# PDMschemE-Car2018.net
KiCad netlist of a schematic drawn in EAGLE
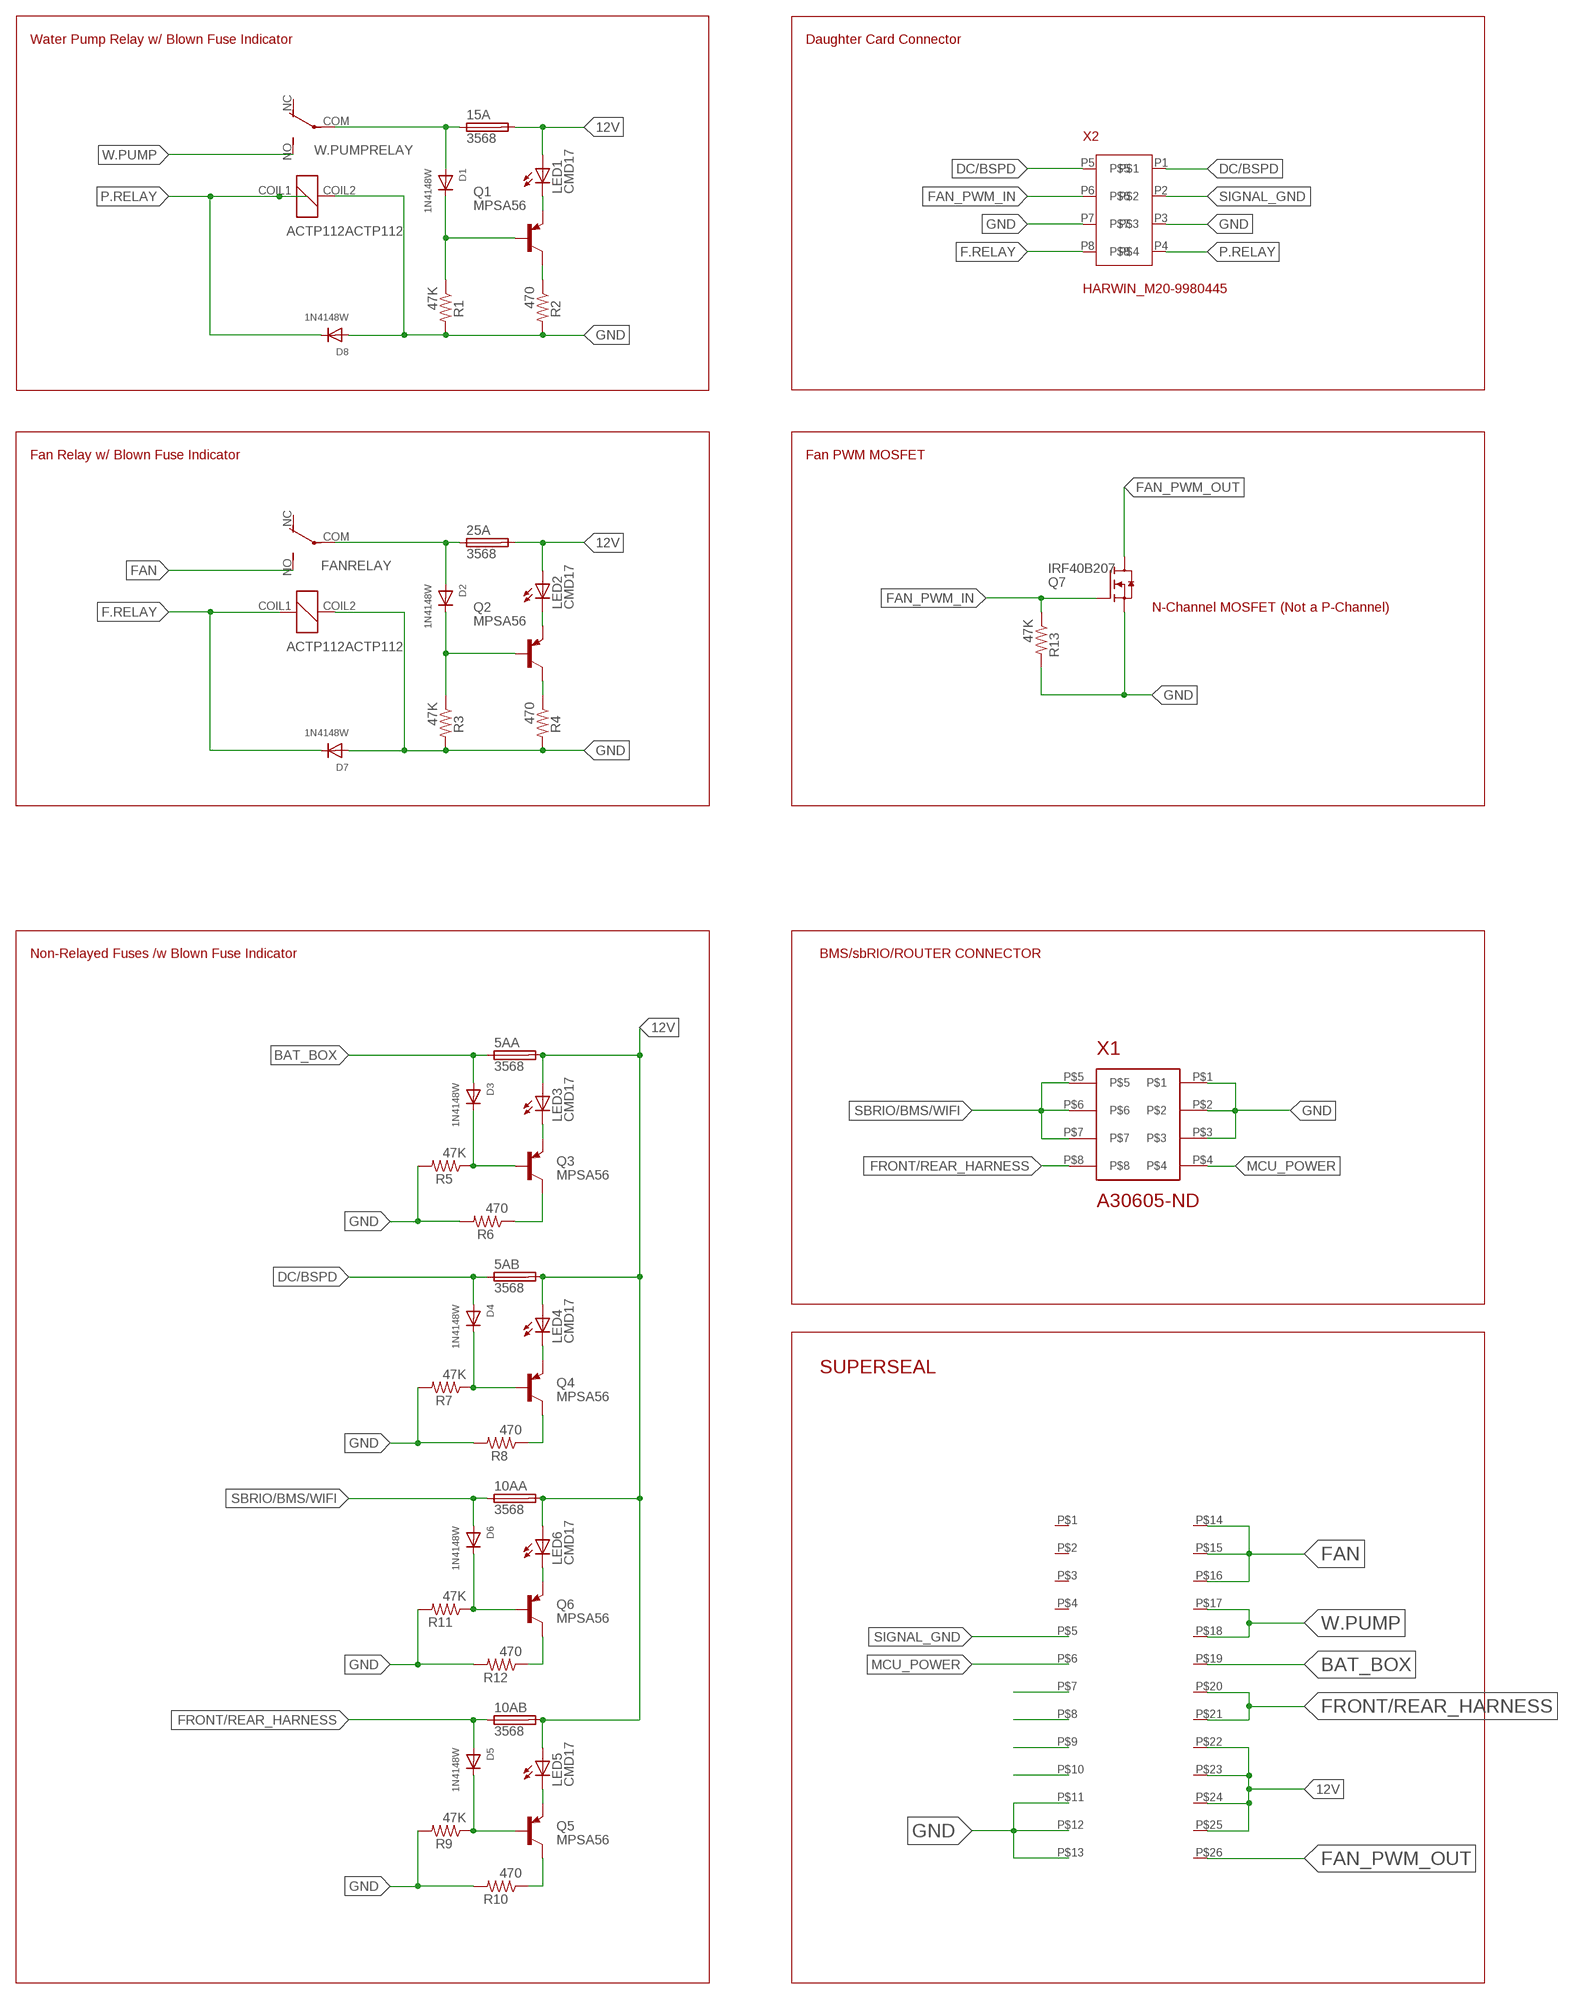
[diagram p0: schematic, sheet 1]

(export (version "E")
  (design (tool "Eeschema 10.0.6"))
  (components
    (comp (ref "5AA")
      (value "3568")
      (footprint "eagle-import:3568")
      (libsource (lib "eagle-import") (part "3568"))
    )
    (comp (ref "5AB")
      (value "3568")
      (footprint "eagle-import:3568")
      (libsource (lib "eagle-import") (part "3568"))
    )
    (comp (ref "10AA")
      (value "3568")
      (footprint "eagle-import:3568")
      (libsource (lib "eagle-import") (part "3568"))
    )
    (comp (ref "10AB")
      (value "3568")
      (footprint "eagle-import:3568")
      (libsource (lib "eagle-import") (part "3568"))
    )
    (comp (ref "15A")
      (value "3568")
      (footprint "eagle-import:3568")
      (libsource (lib "eagle-import") (part "3568"))
    )
    (comp (ref "25A")
      (value "3568")
      (footprint "eagle-import:3568")
      (libsource (lib "eagle-import") (part "3568"))
    )
    (comp (ref "D1")
      (value "1N4148W")
      (footprint "eagle-import:SOD-123")
      (libsource (lib "eagle-import") (part "DIODESOD-123"))
    )
    (comp (ref "D2")
      (value "1N4148W")
      (footprint "eagle-import:SOD-123")
      (libsource (lib "eagle-import") (part "DIODESOD-123"))
    )
    (comp (ref "D3")
      (value "1N4148W")
      (footprint "eagle-import:SOD-123")
      (libsource (lib "eagle-import") (part "DIODESOD-123"))
    )
    (comp (ref "D4")
      (value "1N4148W")
      (footprint "eagle-import:SOD-123")
      (libsource (lib "eagle-import") (part "DIODESOD-123"))
    )
    (comp (ref "D5")
      (value "1N4148W")
      (footprint "eagle-import:SOD-123")
      (libsource (lib "eagle-import") (part "DIODESOD-123"))
    )
    (comp (ref "D6")
      (value "1N4148W")
      (footprint "eagle-import:SOD-123")
      (libsource (lib "eagle-import") (part "DIODESOD-123"))
    )
    (comp (ref "D7")
      (value "1N4148W")
      (footprint "eagle-import:SOD-123")
      (libsource (lib "eagle-import") (part "DIODESOD-123"))
    )
    (comp (ref "D8")
      (value "1N4148W")
      (footprint "eagle-import:SOD-123")
      (libsource (lib "eagle-import") (part "DIODESOD-123"))
    )
    (comp (ref "FANRELAY")
      (value "ACTP112ACTP112")
      (footprint "eagle-import:ACTP112")
      (libsource (lib "eagle-import") (part "ACTP112ACTP112"))
    )
    (comp (ref "LED1")
      (value "CMD17")
      (footprint "eagle-import:CHIPLED_0805")
      (libsource (lib "eagle-import") (part "LEDCHIPLED_0805"))
    )
    (comp (ref "LED2")
      (value "CMD17")
      (footprint "eagle-import:CHIPLED_0805")
      (libsource (lib "eagle-import") (part "LEDCHIPLED_0805"))
    )
    (comp (ref "LED3")
      (value "CMD17")
      (footprint "eagle-import:CHIPLED_0805")
      (libsource (lib "eagle-import") (part "LEDCHIPLED_0805"))
    )
    (comp (ref "LED4")
      (value "CMD17")
      (footprint "eagle-import:CHIPLED_0805")
      (libsource (lib "eagle-import") (part "LEDCHIPLED_0805"))
    )
    (comp (ref "LED5")
      (value "CMD17")
      (footprint "eagle-import:CHIPLED_0805")
      (libsource (lib "eagle-import") (part "LEDCHIPLED_0805"))
    )
    (comp (ref "LED6")
      (value "CMD17")
      (footprint "eagle-import:CHIPLED_0805")
      (libsource (lib "eagle-import") (part "LEDCHIPLED_0805"))
    )
    (comp (ref "Q1")
      (value "MPSA56")
      (footprint "eagle-import:TO92-CBE")
      (libsource (lib "eagle-import") (part "MPSA56"))
    )
    (comp (ref "Q2")
      (value "MPSA56")
      (footprint "eagle-import:TO92-CBE")
      (libsource (lib "eagle-import") (part "MPSA56"))
    )
    (comp (ref "Q3")
      (value "MPSA56")
      (footprint "eagle-import:TO92-CBE")
      (libsource (lib "eagle-import") (part "MPSA56"))
    )
    (comp (ref "Q4")
      (value "MPSA56")
      (footprint "eagle-import:TO92-CBE")
      (libsource (lib "eagle-import") (part "MPSA56"))
    )
    (comp (ref "Q5")
      (value "MPSA56")
      (footprint "eagle-import:TO92-CBE")
      (libsource (lib "eagle-import") (part "MPSA56"))
    )
    (comp (ref "Q6")
      (value "MPSA56")
      (footprint "eagle-import:TO92-CBE")
      (libsource (lib "eagle-import") (part "MPSA56"))
    )
    (comp (ref "Q7")
      (value "IRF40B207")
      (footprint "eagle-import:TO220-3")
      (libsource (lib "eagle-import") (part "IRF40B207"))
    )
    (comp (ref "R1")
      (value "47K")
      (footprint "eagle-import:R1206")
      (libsource (lib "eagle-import") (part "R-US_R1206"))
    )
    (comp (ref "R2")
      (value "470")
      (footprint "eagle-import:R1206")
      (libsource (lib "eagle-import") (part "R-US_R1206"))
    )
    (comp (ref "R3")
      (value "47K")
      (footprint "eagle-import:R1206")
      (libsource (lib "eagle-import") (part "R-US_R1206"))
    )
    (comp (ref "R4")
      (value "470")
      (footprint "eagle-import:R1206")
      (libsource (lib "eagle-import") (part "R-US_R1206"))
    )
    (comp (ref "R5")
      (value "47K")
      (footprint "eagle-import:R1206")
      (libsource (lib "eagle-import") (part "R-US_R1206"))
    )
    (comp (ref "R6")
      (value "470")
      (footprint "eagle-import:R1206")
      (libsource (lib "eagle-import") (part "R-US_R1206"))
    )
    (comp (ref "R7")
      (value "47K")
      (footprint "eagle-import:R1206")
      (libsource (lib "eagle-import") (part "R-US_R1206"))
    )
    (comp (ref "R8")
      (value "470")
      (footprint "eagle-import:R1206")
      (libsource (lib "eagle-import") (part "R-US_R1206"))
    )
    (comp (ref "R9")
      (value "47K")
      (footprint "eagle-import:R1206")
      (libsource (lib "eagle-import") (part "R-US_R1206"))
    )
    (comp (ref "R10")
      (value "470")
      (footprint "eagle-import:R1206")
      (libsource (lib "eagle-import") (part "R-US_R1206"))
    )
    (comp (ref "R11")
      (value "47K")
      (footprint "eagle-import:R1206")
      (libsource (lib "eagle-import") (part "R-US_R1206"))
    )
    (comp (ref "R12")
      (value "470")
      (footprint "eagle-import:R1206")
      (libsource (lib "eagle-import") (part "R-US_R1206"))
    )
    (comp (ref "R13")
      (value "47K")
      (footprint "eagle-import:R1206")
      (libsource (lib "eagle-import") (part "R-US_R1206"))
    )
    (comp (ref "U$4")
      (value "SUPERSEAL1.0_26POS_2ROW")
      (footprint "eagle-import:SUPERSEAL1.0_26POS_2ROW")
      (libsource (lib "eagle-import") (part "SUPERSEAL1.0_26POS_2ROW"))
    )
    (comp (ref "W.PUMPRELAY")
      (value "ACTP112ACTP112")
      (footprint "eagle-import:ACTP112")
      (libsource (lib "eagle-import") (part "ACTP112ACTP112"))
    )
    (comp (ref "X1")
      (value "A30605-ND")
      (footprint "eagle-import:A30605-ND")
      (libsource (lib "eagle-import") (part "A30605-ND"))
    )
    (comp (ref "X2")
      (value "HARWIN_M20-9980445")
      (footprint "eagle-import:HARWIN_M20-9980445")
      (libsource (lib "eagle-import") (part "HARWIN_M20-9980445"))
    )
  )
  (nets
    (net (code "1") (name "12V") (class "Default")
      (node (ref "10AA") (pin "3") (pinfunction "2_3") (pintype "passive"))
      (node (ref "10AA") (pin "4") (pinfunction "2_4") (pintype "passive"))
      (node (ref "10AB") (pin "3") (pinfunction "2_3") (pintype "passive"))
      (node (ref "10AB") (pin "4") (pinfunction "2_4") (pintype "passive"))
      (node (ref "15A") (pin "3") (pinfunction "2_3") (pintype "passive"))
      (node (ref "15A") (pin "4") (pinfunction "2_4") (pintype "passive"))
      (node (ref "25A") (pin "3") (pinfunction "2_3") (pintype "passive"))
      (node (ref "25A") (pin "4") (pinfunction "2_4") (pintype "passive"))
      (node (ref "5AA") (pin "3") (pinfunction "2_3") (pintype "passive"))
      (node (ref "5AA") (pin "4") (pinfunction "2_4") (pintype "passive"))
      (node (ref "5AB") (pin "3") (pinfunction "2_3") (pintype "passive"))
      (node (ref "5AB") (pin "4") (pinfunction "2_4") (pintype "passive"))
      (node (ref "LED1") (pin "A") (pinfunction "A_A") (pintype "passive"))
      (node (ref "LED2") (pin "A") (pinfunction "A_A") (pintype "passive"))
      (node (ref "LED3") (pin "A") (pinfunction "A_A") (pintype "passive"))
      (node (ref "LED4") (pin "A") (pinfunction "A_A") (pintype "passive"))
      (node (ref "LED5") (pin "A") (pinfunction "A_A") (pintype "passive"))
      (node (ref "LED6") (pin "A") (pinfunction "A_A") (pintype "passive"))
      (node (ref "U$4") (pin "P$22") (pinfunction "B22_P$22") (pintype "bidirectional"))
      (node (ref "U$4") (pin "P$23") (pinfunction "B23_P$23") (pintype "bidirectional"))
      (node (ref "U$4") (pin "P$24") (pinfunction "B24_P$24") (pintype "bidirectional"))
      (node (ref "U$4") (pin "P$25") (pinfunction "B25_P$25") (pintype "bidirectional"))
    )
    (net (code "2") (name "BAT_BOX") (class "Default")
      (node (ref "5AA") (pin "1") (pinfunction "1_1") (pintype "passive"))
      (node (ref "5AA") (pin "2") (pinfunction "1_2") (pintype "passive"))
      (node (ref "D3") (pin "A") (pinfunction "A_A") (pintype "passive"))
      (node (ref "U$4") (pin "P$19") (pinfunction "B19_P$19") (pintype "bidirectional"))
    )
    (net (code "3") (name "DC{slash}BSPD") (class "Default")
      (node (ref "5AB") (pin "1") (pinfunction "1_1") (pintype "passive"))
      (node (ref "5AB") (pin "2") (pinfunction "1_2") (pintype "passive"))
      (node (ref "D4") (pin "A") (pinfunction "A_A") (pintype "passive"))
      (node (ref "X2") (pin "P1") (pinfunction "P$1_P1") (pintype "bidirectional"))
      (node (ref "X2") (pin "P5") (pinfunction "P$5_P5") (pintype "bidirectional"))
    )
    (net (code "4") (name "F.RELAY") (class "Default")
      (node (ref "D7") (pin "C") (pinfunction "C_C") (pintype "passive"))
      (node (ref "FANRELAY") (pin "COIL1") (pinfunction "COIL1_COIL1") (pintype "passive"))
      (node (ref "X2") (pin "P8") (pinfunction "P$8_P8") (pintype "bidirectional"))
    )
    (net (code "5") (name "FAN") (class "Default")
      (node (ref "FANRELAY") (pin "NO") (pinfunction "NO_NO") (pintype "passive"))
      (node (ref "U$4") (pin "P$14") (pinfunction "B14_P$14") (pintype "bidirectional"))
      (node (ref "U$4") (pin "P$15") (pinfunction "B15_P$15") (pintype "bidirectional"))
      (node (ref "U$4") (pin "P$16") (pinfunction "B16_P$16") (pintype "bidirectional"))
    )
    (net (code "6") (name "FAN_PWM_IN") (class "Default")
      (node (ref "Q7") (pin "G") (pinfunction "G_G") (pintype "passive"))
      (node (ref "R13") (pin "1") (pinfunction "1_1") (pintype "passive"))
      (node (ref "X2") (pin "P6") (pinfunction "P$6_P6") (pintype "bidirectional"))
    )
    (net (code "7") (name "FAN_PWM_OUT") (class "Default")
      (node (ref "Q7") (pin "D") (pinfunction "D_D") (pintype "passive"))
      (node (ref "U$4") (pin "P$26") (pinfunction "B26_P$26") (pintype "bidirectional"))
    )
    (net (code "8") (name "FRONT{slash}REAR_HARNESS") (class "Default")
      (node (ref "10AB") (pin "1") (pinfunction "1_1") (pintype "passive"))
      (node (ref "10AB") (pin "2") (pinfunction "1_2") (pintype "passive"))
      (node (ref "D5") (pin "A") (pinfunction "A_A") (pintype "passive"))
      (node (ref "U$4") (pin "P$20") (pinfunction "B20_P$20") (pintype "bidirectional"))
      (node (ref "U$4") (pin "P$21") (pinfunction "B21_P$21") (pintype "bidirectional"))
      (node (ref "X1") (pin "P$8") (pinfunction "P$8_P$8") (pintype "bidirectional"))
    )
    (net (code "9") (name "GND") (class "Default")
      (node (ref "D7") (pin "A") (pinfunction "A_A") (pintype "passive"))
      (node (ref "D8") (pin "A") (pinfunction "A_A") (pintype "passive"))
      (node (ref "FANRELAY") (pin "COIL2") (pinfunction "COIL2_COIL2") (pintype "passive"))
      (node (ref "Q7") (pin "S") (pinfunction "S_S") (pintype "passive"))
      (node (ref "R1") (pin "2") (pinfunction "2_2") (pintype "passive"))
      (node (ref "R10") (pin "2") (pinfunction "2_2") (pintype "passive"))
      (node (ref "R11") (pin "2") (pinfunction "2_2") (pintype "passive"))
      (node (ref "R12") (pin "2") (pinfunction "2_2") (pintype "passive"))
      (node (ref "R13") (pin "2") (pinfunction "2_2") (pintype "passive"))
      (node (ref "R2") (pin "2") (pinfunction "2_2") (pintype "passive"))
      (node (ref "R3") (pin "2") (pinfunction "2_2") (pintype "passive"))
      (node (ref "R4") (pin "2") (pinfunction "2_2") (pintype "passive"))
      (node (ref "R5") (pin "2") (pinfunction "2_2") (pintype "passive"))
      (node (ref "R6") (pin "2") (pinfunction "2_2") (pintype "passive"))
      (node (ref "R7") (pin "2") (pinfunction "2_2") (pintype "passive"))
      (node (ref "R8") (pin "2") (pinfunction "2_2") (pintype "passive"))
      (node (ref "R9") (pin "2") (pinfunction "2_2") (pintype "passive"))
      (node (ref "U$4") (pin "P$11") (pinfunction "B11_P$11") (pintype "bidirectional"))
      (node (ref "U$4") (pin "P$12") (pinfunction "B12_P$12") (pintype "bidirectional"))
      (node (ref "U$4") (pin "P$13") (pinfunction "B13_P$13") (pintype "bidirectional"))
      (node (ref "W.PUMPRELAY") (pin "COIL2") (pinfunction "COIL2_COIL2") (pintype "passive"))
      (node (ref "X1") (pin "P$1") (pinfunction "P$1_P$1") (pintype "bidirectional"))
      (node (ref "X1") (pin "P$2") (pinfunction "P$2_P$2") (pintype "bidirectional"))
      (node (ref "X1") (pin "P$3") (pinfunction "P$3_P$3") (pintype "bidirectional"))
      (node (ref "X2") (pin "P3") (pinfunction "P$3_P3") (pintype "bidirectional"))
      (node (ref "X2") (pin "P7") (pinfunction "P$7_P7") (pintype "bidirectional"))
    )
    (net (code "10") (name "MCU_POWER") (class "Default")
      (node (ref "U$4") (pin "P$6") (pinfunction "B6_P$6") (pintype "bidirectional"))
      (node (ref "X1") (pin "P$4") (pinfunction "P$4_P$4") (pintype "bidirectional"))
    )
    (net (code "11") (name "Net-(15A-1-Pad2)") (class "Default")
      (node (ref "15A") (pin "1") (pinfunction "1_1") (pintype "passive"))
      (node (ref "15A") (pin "2") (pinfunction "1_2") (pintype "passive"))
      (node (ref "D1") (pin "A") (pinfunction "A_A") (pintype "passive"))
      (node (ref "W.PUMPRELAY") (pin "COM") (pinfunction "COM_COM") (pintype "passive"))
    )
    (net (code "12") (name "Net-(25A-1-Pad2)") (class "Default")
      (node (ref "25A") (pin "1") (pinfunction "1_1") (pintype "passive"))
      (node (ref "25A") (pin "2") (pinfunction "1_2") (pintype "passive"))
      (node (ref "D2") (pin "A") (pinfunction "A_A") (pintype "passive"))
      (node (ref "FANRELAY") (pin "COM") (pinfunction "COM_COM") (pintype "passive"))
    )
    (net (code "13") (name "Net-(D1-PadC)") (class "Default")
      (node (ref "D1") (pin "C") (pinfunction "C_C") (pintype "passive"))
      (node (ref "Q1") (pin "B") (pinfunction "B_B") (pintype "passive"))
      (node (ref "R1") (pin "1") (pinfunction "1_1") (pintype "passive"))
    )
    (net (code "14") (name "Net-(D2-PadC)") (class "Default")
      (node (ref "D2") (pin "C") (pinfunction "C_C") (pintype "passive"))
      (node (ref "Q2") (pin "B") (pinfunction "B_B") (pintype "passive"))
      (node (ref "R3") (pin "1") (pinfunction "1_1") (pintype "passive"))
    )
    (net (code "15") (name "Net-(D3-PadC)") (class "Default")
      (node (ref "D3") (pin "C") (pinfunction "C_C") (pintype "passive"))
      (node (ref "Q3") (pin "B") (pinfunction "B_B") (pintype "passive"))
      (node (ref "R5") (pin "1") (pinfunction "1_1") (pintype "passive"))
    )
    (net (code "16") (name "Net-(D4-PadC)") (class "Default")
      (node (ref "D4") (pin "C") (pinfunction "C_C") (pintype "passive"))
      (node (ref "Q4") (pin "B") (pinfunction "B_B") (pintype "passive"))
      (node (ref "R7") (pin "1") (pinfunction "1_1") (pintype "passive"))
    )
    (net (code "17") (name "Net-(D5-PadC)") (class "Default")
      (node (ref "D5") (pin "C") (pinfunction "C_C") (pintype "passive"))
      (node (ref "Q5") (pin "B") (pinfunction "B_B") (pintype "passive"))
      (node (ref "R9") (pin "1") (pinfunction "1_1") (pintype "passive"))
    )
    (net (code "18") (name "Net-(D6-PadC)") (class "Default")
      (node (ref "D6") (pin "C") (pinfunction "C_C") (pintype "passive"))
      (node (ref "Q6") (pin "B") (pinfunction "B_B") (pintype "passive"))
      (node (ref "R11") (pin "1") (pinfunction "1_1") (pintype "passive"))
    )
    (net (code "19") (name "Net-(LED1-PadC)") (class "Default")
      (node (ref "LED1") (pin "C") (pinfunction "C_C") (pintype "passive"))
      (node (ref "Q1") (pin "E") (pinfunction "E_E") (pintype "passive"))
    )
    (net (code "20") (name "Net-(LED2-PadC)") (class "Default")
      (node (ref "LED2") (pin "C") (pinfunction "C_C") (pintype "passive"))
      (node (ref "Q2") (pin "E") (pinfunction "E_E") (pintype "passive"))
    )
    (net (code "21") (name "Net-(LED3-PadC)") (class "Default")
      (node (ref "LED3") (pin "C") (pinfunction "C_C") (pintype "passive"))
      (node (ref "Q3") (pin "E") (pinfunction "E_E") (pintype "passive"))
    )
    (net (code "22") (name "Net-(LED4-PadC)") (class "Default")
      (node (ref "LED4") (pin "C") (pinfunction "C_C") (pintype "passive"))
      (node (ref "Q4") (pin "E") (pinfunction "E_E") (pintype "passive"))
    )
    (net (code "23") (name "Net-(LED5-PadC)") (class "Default")
      (node (ref "LED5") (pin "C") (pinfunction "C_C") (pintype "passive"))
      (node (ref "Q5") (pin "E") (pinfunction "E_E") (pintype "passive"))
    )
    (net (code "24") (name "Net-(LED6-PadC)") (class "Default")
      (node (ref "LED6") (pin "C") (pinfunction "C_C") (pintype "passive"))
      (node (ref "Q6") (pin "E") (pinfunction "E_E") (pintype "passive"))
    )
    (net (code "25") (name "Net-(Q1-PadC)") (class "Default")
      (node (ref "Q1") (pin "C") (pinfunction "C_C") (pintype "passive"))
      (node (ref "R2") (pin "1") (pinfunction "1_1") (pintype "passive"))
    )
    (net (code "26") (name "Net-(Q2-PadC)") (class "Default")
      (node (ref "Q2") (pin "C") (pinfunction "C_C") (pintype "passive"))
      (node (ref "R4") (pin "1") (pinfunction "1_1") (pintype "passive"))
    )
    (net (code "27") (name "Net-(Q3-PadC)") (class "Default")
      (node (ref "Q3") (pin "C") (pinfunction "C_C") (pintype "passive"))
      (node (ref "R6") (pin "1") (pinfunction "1_1") (pintype "passive"))
    )
    (net (code "28") (name "Net-(Q4-PadC)") (class "Default")
      (node (ref "Q4") (pin "C") (pinfunction "C_C") (pintype "passive"))
      (node (ref "R8") (pin "1") (pinfunction "1_1") (pintype "passive"))
    )
    (net (code "29") (name "Net-(Q5-PadC)") (class "Default")
      (node (ref "Q5") (pin "C") (pinfunction "C_C") (pintype "passive"))
      (node (ref "R10") (pin "1") (pinfunction "1_1") (pintype "passive"))
    )
    (net (code "30") (name "Net-(Q6-PadC)") (class "Default")
      (node (ref "Q6") (pin "C") (pinfunction "C_C") (pintype "passive"))
      (node (ref "R12") (pin "1") (pinfunction "1_1") (pintype "passive"))
    )
    (net (code "31") (name "P.RELAY") (class "Default")
      (node (ref "D8") (pin "C") (pinfunction "C_C") (pintype "passive"))
      (node (ref "W.PUMPRELAY") (pin "COIL1") (pinfunction "COIL1_COIL1") (pintype "passive"))
      (node (ref "X2") (pin "P4") (pinfunction "P$4_P4") (pintype "bidirectional"))
    )
    (net (code "32") (name "SBRIO{slash}BMS{slash}WIFI") (class "Default")
      (node (ref "10AA") (pin "1") (pinfunction "1_1") (pintype "passive"))
      (node (ref "10AA") (pin "2") (pinfunction "1_2") (pintype "passive"))
      (node (ref "D6") (pin "A") (pinfunction "A_A") (pintype "passive"))
      (node (ref "X1") (pin "P$5") (pinfunction "P$5_P$5") (pintype "bidirectional"))
      (node (ref "X1") (pin "P$6") (pinfunction "P$6_P$6") (pintype "bidirectional"))
      (node (ref "X1") (pin "P$7") (pinfunction "P$7_P$7") (pintype "bidirectional"))
    )
    (net (code "33") (name "SIGNAL_GND") (class "Default")
      (node (ref "U$4") (pin "P$5") (pinfunction "B5_P$5") (pintype "bidirectional"))
      (node (ref "X2") (pin "P2") (pinfunction "P$2_P2") (pintype "bidirectional"))
    )
    (net (code "34") (name "W.PUMP") (class "Default")
      (node (ref "U$4") (pin "P$17") (pinfunction "B17_P$17") (pintype "bidirectional"))
      (node (ref "U$4") (pin "P$18") (pinfunction "B18_P$18") (pintype "bidirectional"))
      (node (ref "W.PUMPRELAY") (pin "NO") (pinfunction "NO_NO") (pintype "passive"))
    )
    (net (code "35") (name "unconnected-(FANRELAY-PadNC)") (class "Default")
      (node (ref "FANRELAY") (pin "NC") (pinfunction "NC_NC") (pintype "passive"))
    )
    (net (code "36") (name "unconnected-(U$4-B1-PadP$1)") (class "Default")
      (node (ref "U$4") (pin "P$1") (pinfunction "B1_P$1") (pintype "bidirectional"))
    )
    (net (code "37") (name "unconnected-(U$4-B2-PadP$2)") (class "Default")
      (node (ref "U$4") (pin "P$2") (pinfunction "B2_P$2") (pintype "bidirectional"))
    )
    (net (code "38") (name "unconnected-(U$4-B3-PadP$3)") (class "Default")
      (node (ref "U$4") (pin "P$3") (pinfunction "B3_P$3") (pintype "bidirectional"))
    )
    (net (code "39") (name "unconnected-(U$4-B4-PadP$4)") (class "Default")
      (node (ref "U$4") (pin "P$4") (pinfunction "B4_P$4") (pintype "bidirectional"))
    )
    (net (code "40") (name "unconnected-(U$4-B7-PadP$7)") (class "Default")
      (node (ref "U$4") (pin "P$7") (pinfunction "B7_P$7") (pintype "bidirectional"))
    )
    (net (code "41") (name "unconnected-(U$4-B8-PadP$8)") (class "Default")
      (node (ref "U$4") (pin "P$8") (pinfunction "B8_P$8") (pintype "bidirectional"))
    )
    (net (code "42") (name "unconnected-(U$4-B9-PadP$9)") (class "Default")
      (node (ref "U$4") (pin "P$9") (pinfunction "B9_P$9") (pintype "bidirectional"))
    )
    (net (code "43") (name "unconnected-(U$4-B10-PadP$10)") (class "Default")
      (node (ref "U$4") (pin "P$10") (pinfunction "B10_P$10") (pintype "bidirectional"))
    )
    (net (code "44") (name "unconnected-(W.PUMPRELAY-PadNC)") (class "Default")
      (node (ref "W.PUMPRELAY") (pin "NC") (pinfunction "NC_NC") (pintype "passive"))
    )
  )
)
